# Selector_Gain.net
KiCad netlist of a schematic drawn in EAGLE
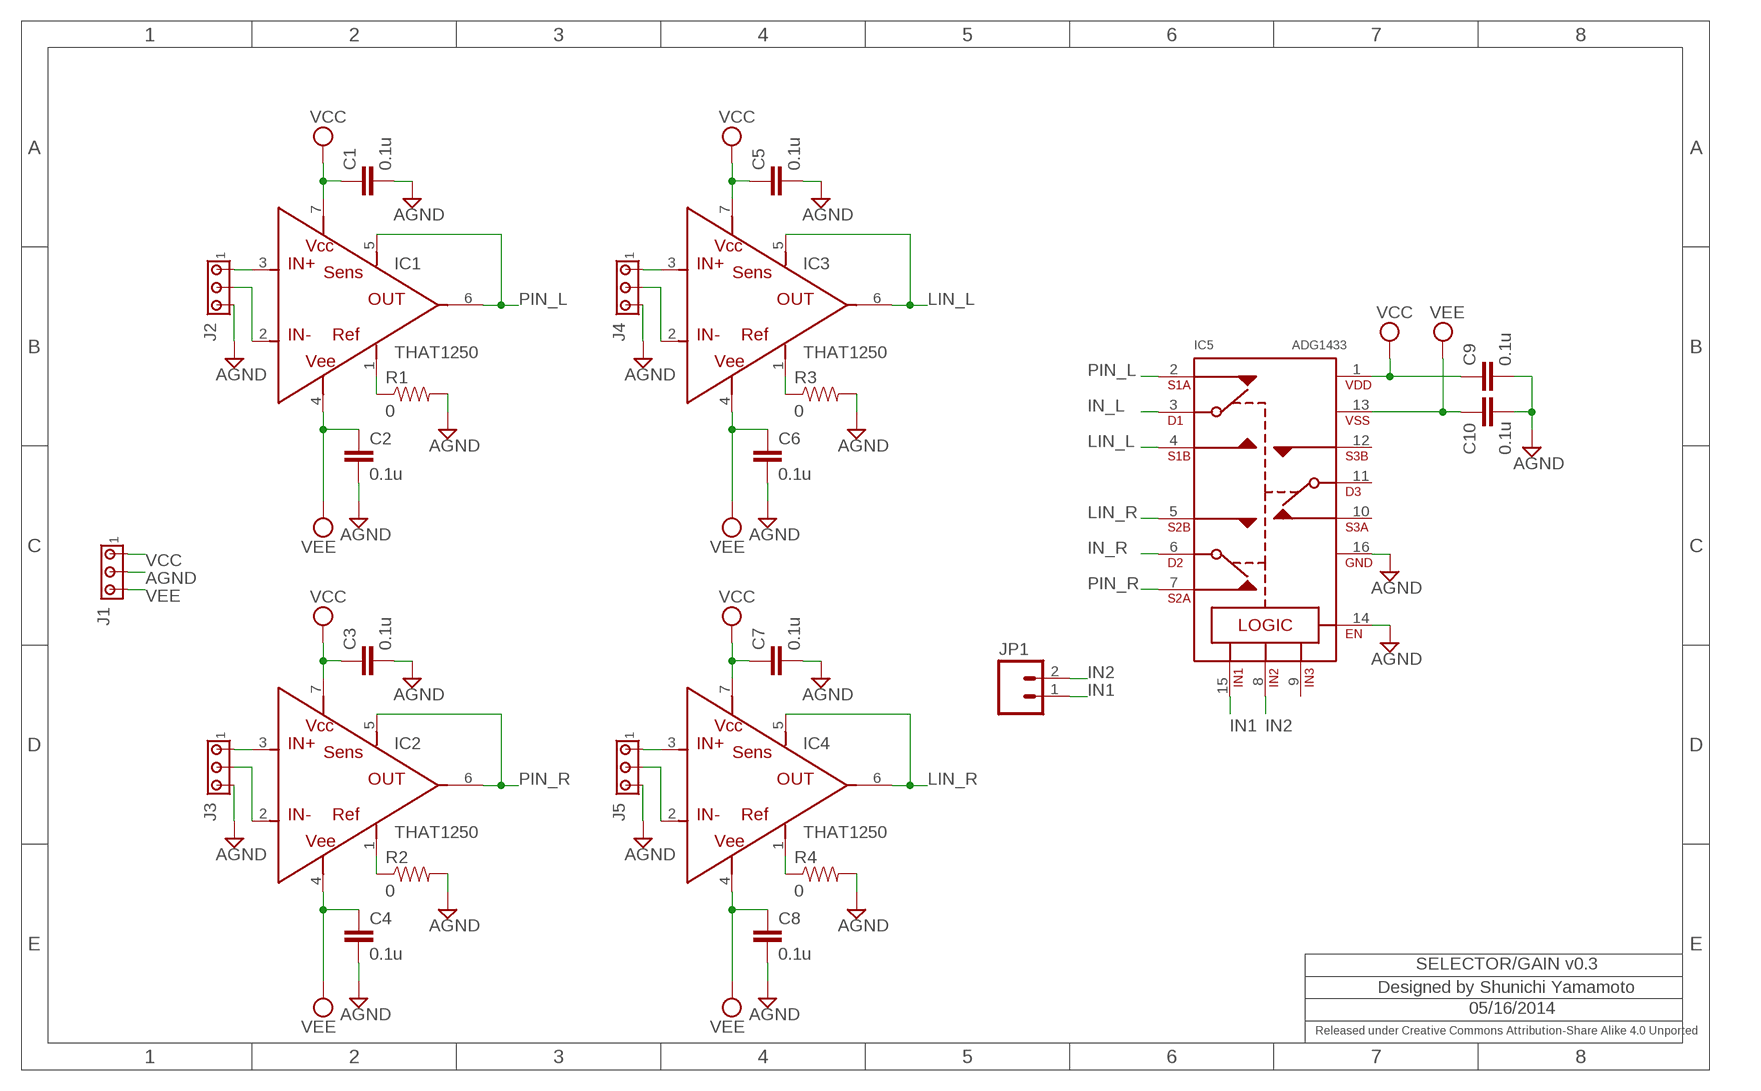
[diagram p0: schematic, sheet 1]
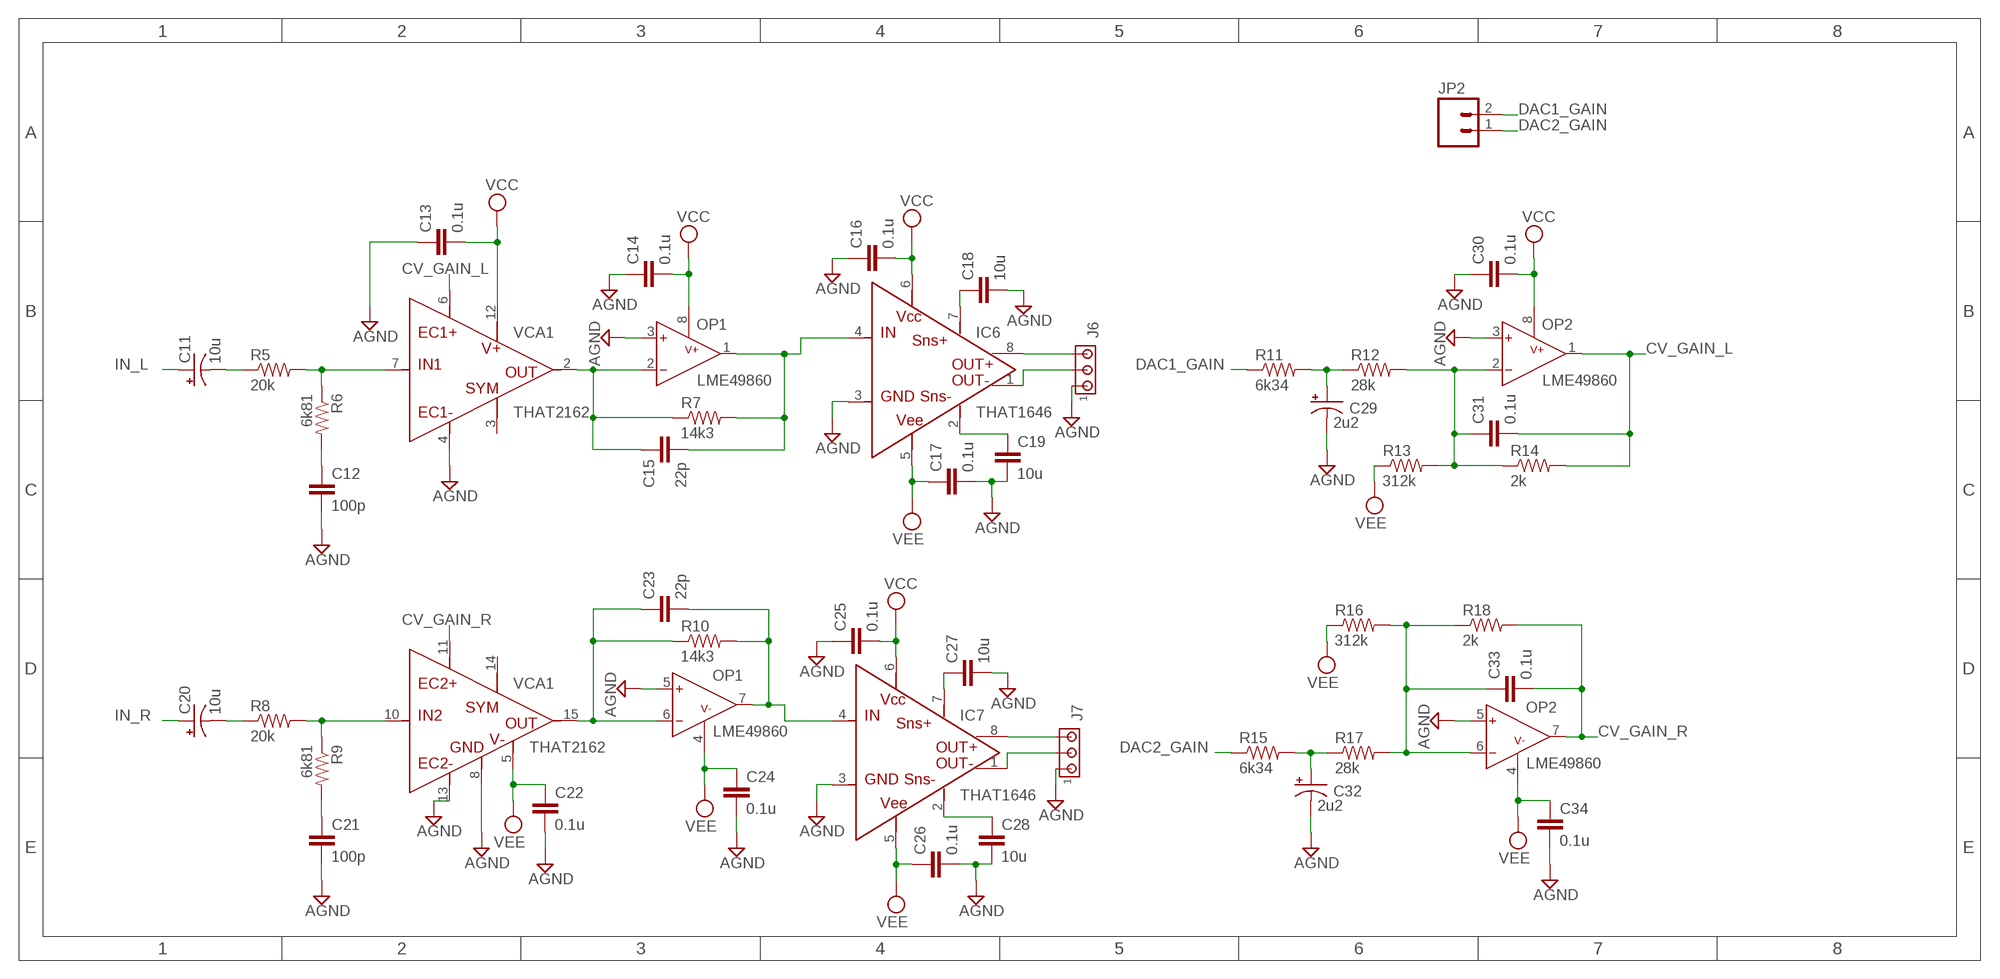
[diagram p1: schematic, sheet 2]

(export (version "E")
  (design (tool "Eeschema 10.0.6"))
  (components
    (comp (ref "C11")
      (value "10u")
      (footprint "eagle-import:UD-5X5,8_NICHICON")
      (libsource (lib "eagle-import") (part "CPOL-USUD-5X5,8"))
    )
    (comp (ref "C12")
      (value "100p")
      (footprint "eagle-import:C2012")
      (libsource (lib "eagle-import") (part "C-EUC2012"))
    )
    (comp (ref "C13")
      (value "0.1u")
      (footprint "eagle-import:C2012")
      (libsource (lib "eagle-import") (part "C-EUC2012"))
    )
    (comp (ref "C14")
      (value "0.1u")
      (footprint "eagle-import:C2012")
      (libsource (lib "eagle-import") (part "C-EUC2012"))
    )
    (comp (ref "C15")
      (value "22p")
      (footprint "eagle-import:C2012")
      (libsource (lib "eagle-import") (part "C-EUC2012"))
    )
    (comp (ref "C16")
      (value "0.1u")
      (footprint "eagle-import:C2012")
      (libsource (lib "eagle-import") (part "C-EUC2012"))
    )
    (comp (ref "C17")
      (value "0.1u")
      (footprint "eagle-import:C2012")
      (libsource (lib "eagle-import") (part "C-EUC2012"))
    )
    (comp (ref "C18")
      (value "10u")
      (footprint "eagle-import:C2012")
      (libsource (lib "eagle-import") (part "C-EUC2012"))
    )
    (comp (ref "C19")
      (value "10u")
      (footprint "eagle-import:C2012")
      (libsource (lib "eagle-import") (part "C-EUC2012"))
    )
    (comp (ref "C20")
      (value "10u")
      (footprint "eagle-import:UD-5X5,8_NICHICON")
      (libsource (lib "eagle-import") (part "CPOL-USUD-5X5,8"))
    )
    (comp (ref "C21")
      (value "100p")
      (footprint "eagle-import:C2012")
      (libsource (lib "eagle-import") (part "C-EUC2012"))
    )
    (comp (ref "C22")
      (value "0.1u")
      (footprint "eagle-import:C2012")
      (libsource (lib "eagle-import") (part "C-EUC2012"))
    )
    (comp (ref "C23")
      (value "22p")
      (footprint "eagle-import:C2012")
      (libsource (lib "eagle-import") (part "C-EUC2012"))
    )
    (comp (ref "C24")
      (value "0.1u")
      (footprint "eagle-import:C2012")
      (libsource (lib "eagle-import") (part "C-EUC2012"))
    )
    (comp (ref "C25")
      (value "0.1u")
      (footprint "eagle-import:C2012")
      (libsource (lib "eagle-import") (part "C-EUC2012"))
    )
    (comp (ref "C26")
      (value "0.1u")
      (footprint "eagle-import:C2012")
      (libsource (lib "eagle-import") (part "C-EUC2012"))
    )
    (comp (ref "C27")
      (value "10u")
      (footprint "eagle-import:C2012")
      (libsource (lib "eagle-import") (part "C-EUC2012"))
    )
    (comp (ref "C28")
      (value "10u")
      (footprint "eagle-import:C2012")
      (libsource (lib "eagle-import") (part "C-EUC2012"))
    )
    (comp (ref "C29")
      (value "2u2")
      (footprint "eagle-import:UD-5X5,8_NICHICON")
      (libsource (lib "eagle-import") (part "CPOL-USUD-5X5,8"))
    )
    (comp (ref "C30")
      (value "0.1u")
      (footprint "eagle-import:C2012")
      (libsource (lib "eagle-import") (part "C-EUC2012"))
    )
    (comp (ref "C31")
      (value "0.1u")
      (footprint "eagle-import:C2012")
      (libsource (lib "eagle-import") (part "C-EUC2012"))
    )
    (comp (ref "C32")
      (value "2u2")
      (footprint "eagle-import:UD-5X5,8_NICHICON")
      (libsource (lib "eagle-import") (part "CPOL-USUD-5X5,8"))
    )
    (comp (ref "C33")
      (value "0.1u")
      (footprint "eagle-import:C2012")
      (libsource (lib "eagle-import") (part "C-EUC2012"))
    )
    (comp (ref "C34")
      (value "0.1u")
      (footprint "eagle-import:C2012")
      (libsource (lib "eagle-import") (part "C-EUC2012"))
    )
    (comp (ref "IC6")
      (value "THAT1646")
      (footprint "eagle-import:SOIC8")
      (libsource (lib "eagle-import") (part "THAT1646"))
    )
    (comp (ref "IC7")
      (value "THAT1646")
      (footprint "eagle-import:SOIC8")
      (libsource (lib "eagle-import") (part "THAT1646"))
    )
    (comp (ref "J6")
      (value "MTA03-100")
      (footprint "eagle-import:10X03MTA")
      (libsource (lib "eagle-import") (part "MTA03-100"))
    )
    (comp (ref "J7")
      (value "MTA03-100")
      (footprint "eagle-import:10X03MTA")
      (libsource (lib "eagle-import") (part "MTA03-100"))
    )
    (comp (ref "JP2")
      (value "M02PTH")
      (footprint "eagle-import:1X02")
      (libsource (lib "eagle-import") (part "M02PTH"))
    )
    (comp (ref "OP1")
      (value "LME49860")
      (footprint "eagle-import:SOIC8")
      (libsource (lib "eagle-import") (part "LME49860"))
    )
    (comp (ref "OP2")
      (value "LME49860")
      (footprint "eagle-import:SOIC8")
      (libsource (lib "eagle-import") (part "LME49860"))
    )
    (comp (ref "R5")
      (value "20k")
      (footprint "eagle-import:0805")
      (libsource (lib "eagle-import") (part "RESISTOR0805-RES"))
    )
    (comp (ref "R6")
      (value "6k81")
      (footprint "eagle-import:0805")
      (libsource (lib "eagle-import") (part "RESISTOR0805-RES"))
    )
    (comp (ref "R7")
      (value "14k3")
      (footprint "eagle-import:0805")
      (libsource (lib "eagle-import") (part "RESISTOR0805-RES"))
    )
    (comp (ref "R8")
      (value "20k")
      (footprint "eagle-import:0805")
      (libsource (lib "eagle-import") (part "RESISTOR0805-RES"))
    )
    (comp (ref "R9")
      (value "6k81")
      (footprint "eagle-import:0805")
      (libsource (lib "eagle-import") (part "RESISTOR0805-RES"))
    )
    (comp (ref "R10")
      (value "14k3")
      (footprint "eagle-import:0805")
      (libsource (lib "eagle-import") (part "RESISTOR0805-RES"))
    )
    (comp (ref "R11")
      (value "6k34")
      (footprint "eagle-import:0805")
      (libsource (lib "eagle-import") (part "RESISTOR0805-RES"))
    )
    (comp (ref "R12")
      (value "28k")
      (footprint "eagle-import:0805")
      (libsource (lib "eagle-import") (part "RESISTOR0805-RES"))
    )
    (comp (ref "R13")
      (value "312k")
      (footprint "eagle-import:0805")
      (libsource (lib "eagle-import") (part "RESISTOR0805-RES"))
    )
    (comp (ref "R14")
      (value "2k")
      (footprint "eagle-import:0805")
      (libsource (lib "eagle-import") (part "RESISTOR0805-RES"))
    )
    (comp (ref "R15")
      (value "6k34")
      (footprint "eagle-import:0805")
      (libsource (lib "eagle-import") (part "RESISTOR0805-RES"))
    )
    (comp (ref "R16")
      (value "312k")
      (footprint "eagle-import:0805")
      (libsource (lib "eagle-import") (part "RESISTOR0805-RES"))
    )
    (comp (ref "R17")
      (value "28k")
      (footprint "eagle-import:0805")
      (libsource (lib "eagle-import") (part "RESISTOR0805-RES"))
    )
    (comp (ref "R18")
      (value "2k")
      (footprint "eagle-import:0805")
      (libsource (lib "eagle-import") (part "RESISTOR0805-RES"))
    )
    (comp (ref "VCA1")
      (value "THAT2162")
      (footprint "eagle-import:QSOP-16")
      (libsource (lib "eagle-import") (part "THAT2162"))
    )
    (comp (ref "C1")
      (value "0.1u")
      (footprint "eagle-import:C2012")
      (libsource (lib "eagle-import") (part "C-EUC2012"))
    )
    (comp (ref "C2")
      (value "0.1u")
      (footprint "eagle-import:C2012")
      (libsource (lib "eagle-import") (part "C-EUC2012"))
    )
    (comp (ref "C3")
      (value "0.1u")
      (footprint "eagle-import:C2012")
      (libsource (lib "eagle-import") (part "C-EUC2012"))
    )
    (comp (ref "C4")
      (value "0.1u")
      (footprint "eagle-import:C2012")
      (libsource (lib "eagle-import") (part "C-EUC2012"))
    )
    (comp (ref "C5")
      (value "0.1u")
      (footprint "eagle-import:C2012")
      (libsource (lib "eagle-import") (part "C-EUC2012"))
    )
    (comp (ref "C6")
      (value "0.1u")
      (footprint "eagle-import:C2012")
      (libsource (lib "eagle-import") (part "C-EUC2012"))
    )
    (comp (ref "C7")
      (value "0.1u")
      (footprint "eagle-import:C2012")
      (libsource (lib "eagle-import") (part "C-EUC2012"))
    )
    (comp (ref "C8")
      (value "0.1u")
      (footprint "eagle-import:C2012")
      (libsource (lib "eagle-import") (part "C-EUC2012"))
    )
    (comp (ref "C9")
      (value "0.1u")
      (footprint "eagle-import:C2012")
      (libsource (lib "eagle-import") (part "C-EUC2012"))
    )
    (comp (ref "C10")
      (value "0.1u")
      (footprint "eagle-import:C2012")
      (libsource (lib "eagle-import") (part "C-EUC2012"))
    )
    (comp (ref "IC1")
      (value "THAT1250")
      (footprint "eagle-import:SOIC8")
      (libsource (lib "eagle-import") (part "THAT1250"))
    )
    (comp (ref "IC2")
      (value "THAT1250")
      (footprint "eagle-import:SOIC8")
      (libsource (lib "eagle-import") (part "THAT1250"))
    )
    (comp (ref "IC3")
      (value "THAT1250")
      (footprint "eagle-import:SOIC8")
      (libsource (lib "eagle-import") (part "THAT1250"))
    )
    (comp (ref "IC4")
      (value "THAT1250")
      (footprint "eagle-import:SOIC8")
      (libsource (lib "eagle-import") (part "THAT1250"))
    )
    (comp (ref "IC5")
      (value "ADG1433")
      (footprint "eagle-import:TSSOP16")
      (libsource (lib "eagle-import") (part "ADG1433"))
    )
    (comp (ref "J1")
      (value "MTA03-156")
      (footprint "eagle-import:1X3MTA")
      (libsource (lib "eagle-import") (part "MTA03-156"))
    )
    (comp (ref "J2")
      (value "MTA03-100")
      (footprint "eagle-import:10X03MTA")
      (libsource (lib "eagle-import") (part "MTA03-100"))
    )
    (comp (ref "J3")
      (value "MTA03-100")
      (footprint "eagle-import:10X03MTA")
      (libsource (lib "eagle-import") (part "MTA03-100"))
    )
    (comp (ref "J4")
      (value "MTA03-100")
      (footprint "eagle-import:10X03MTA")
      (libsource (lib "eagle-import") (part "MTA03-100"))
    )
    (comp (ref "J5")
      (value "MTA03-100")
      (footprint "eagle-import:10X03MTA")
      (libsource (lib "eagle-import") (part "MTA03-100"))
    )
    (comp (ref "JP1")
      (value "M02PTH")
      (footprint "eagle-import:1X02")
      (libsource (lib "eagle-import") (part "M02PTH"))
    )
    (comp (ref "R1")
      (value "0")
      (footprint "eagle-import:0805")
      (libsource (lib "eagle-import") (part "RESISTOR0805-RES"))
    )
    (comp (ref "R2")
      (value "0")
      (footprint "eagle-import:0805")
      (libsource (lib "eagle-import") (part "RESISTOR0805-RES"))
    )
    (comp (ref "R3")
      (value "0")
      (footprint "eagle-import:0805")
      (libsource (lib "eagle-import") (part "RESISTOR0805-RES"))
    )
    (comp (ref "R4")
      (value "0")
      (footprint "eagle-import:0805")
      (libsource (lib "eagle-import") (part "RESISTOR0805-RES"))
    )
  )
  (nets
    (net (code "1") (name "AGND") (class "Default")
      (node (ref "C1") (pin "2") (pinfunction "2_2") (pintype "passive"))
      (node (ref "C10") (pin "2") (pinfunction "2_2") (pintype "passive"))
      (node (ref "C12") (pin "2") (pinfunction "2_2") (pintype "passive"))
      (node (ref "C13") (pin "1") (pinfunction "1_1") (pintype "passive"))
      (node (ref "C14") (pin "1") (pinfunction "1_1") (pintype "passive"))
      (node (ref "C16") (pin "1") (pinfunction "1_1") (pintype "passive"))
      (node (ref "C17") (pin "2") (pinfunction "2_2") (pintype "passive"))
      (node (ref "C18") (pin "2") (pinfunction "2_2") (pintype "passive"))
      (node (ref "C19") (pin "2") (pinfunction "2_2") (pintype "passive"))
      (node (ref "C2") (pin "2") (pinfunction "2_2") (pintype "passive"))
      (node (ref "C21") (pin "2") (pinfunction "2_2") (pintype "passive"))
      (node (ref "C22") (pin "2") (pinfunction "2_2") (pintype "passive"))
      (node (ref "C24") (pin "2") (pinfunction "2_2") (pintype "passive"))
      (node (ref "C25") (pin "1") (pinfunction "1_1") (pintype "passive"))
      (node (ref "C26") (pin "2") (pinfunction "2_2") (pintype "passive"))
      (node (ref "C27") (pin "2") (pinfunction "2_2") (pintype "passive"))
      (node (ref "C28") (pin "2") (pinfunction "2_2") (pintype "passive"))
      (node (ref "C29") (pin "-") (pinfunction "-_-") (pintype "passive"))
      (node (ref "C3") (pin "2") (pinfunction "2_2") (pintype "passive"))
      (node (ref "C30") (pin "1") (pinfunction "1_1") (pintype "passive"))
      (node (ref "C32") (pin "-") (pinfunction "-_-") (pintype "passive"))
      (node (ref "C34") (pin "2") (pinfunction "2_2") (pintype "passive"))
      (node (ref "C4") (pin "2") (pinfunction "2_2") (pintype "passive"))
      (node (ref "C5") (pin "2") (pinfunction "2_2") (pintype "passive"))
      (node (ref "C6") (pin "2") (pinfunction "2_2") (pintype "passive"))
      (node (ref "C7") (pin "2") (pinfunction "2_2") (pintype "passive"))
      (node (ref "C8") (pin "2") (pinfunction "2_2") (pintype "passive"))
      (node (ref "C9") (pin "2") (pinfunction "2_2") (pintype "passive"))
      (node (ref "IC5") (pin "14") (pinfunction "EN_14") (pintype "bidirectional"))
      (node (ref "IC5") (pin "16") (pinfunction "GND_16") (pintype "bidirectional"))
      (node (ref "IC6") (pin "3") (pinfunction "GND_3") (pintype "input"))
      (node (ref "IC7") (pin "3") (pinfunction "GND_3") (pintype "input"))
      (node (ref "J1") (pin "2") (pinfunction "2_2") (pintype "passive"))
      (node (ref "J2") (pin "3") (pinfunction "3_3") (pintype "passive"))
      (node (ref "J3") (pin "3") (pinfunction "3_3") (pintype "passive"))
      (node (ref "J4") (pin "3") (pinfunction "3_3") (pintype "passive"))
      (node (ref "J5") (pin "3") (pinfunction "3_3") (pintype "passive"))
      (node (ref "J6") (pin "1") (pinfunction "1_1") (pintype "passive"))
      (node (ref "J7") (pin "1") (pinfunction "1_1") (pintype "passive"))
      (node (ref "OP1") (pin "3") (pinfunction "INA+_3") (pintype "input"))
      (node (ref "OP1") (pin "5") (pinfunction "INB+_5") (pintype "input"))
      (node (ref "OP2") (pin "3") (pinfunction "INA+_3") (pintype "input"))
      (node (ref "OP2") (pin "5") (pinfunction "INB+_5") (pintype "input"))
      (node (ref "R1") (pin "2") (pinfunction "2_2") (pintype "passive"))
      (node (ref "R2") (pin "2") (pinfunction "2_2") (pintype "passive"))
      (node (ref "R3") (pin "2") (pinfunction "2_2") (pintype "passive"))
      (node (ref "R4") (pin "2") (pinfunction "2_2") (pintype "passive"))
      (node (ref "VCA1") (pin "13") (pinfunction "EC2-_13") (pintype "power_in"))
      (node (ref "VCA1") (pin "4") (pinfunction "EC1-_4") (pintype "input"))
      (node (ref "VCA1") (pin "8") (pinfunction "GND_8") (pintype "input"))
    )
    (net (code "2") (name "CV_GAIN_L") (class "Default")
      (node (ref "C31") (pin "2") (pinfunction "2_2") (pintype "passive"))
      (node (ref "OP2") (pin "1") (pinfunction "OUTA_1") (pintype "output"))
      (node (ref "R14") (pin "2") (pinfunction "2_2") (pintype "passive"))
      (node (ref "VCA1") (pin "6") (pinfunction "EC1+_6") (pintype "bidirectional"))
    )
    (net (code "3") (name "CV_GAIN_R") (class "Default")
      (node (ref "C33") (pin "2") (pinfunction "2_2") (pintype "passive"))
      (node (ref "OP2") (pin "7") (pinfunction "OUTB_7") (pintype "output"))
      (node (ref "R18") (pin "2") (pinfunction "2_2") (pintype "passive"))
      (node (ref "VCA1") (pin "11") (pinfunction "EC2+_11") (pintype "input"))
    )
    (net (code "4") (name "DAC1_GAIN") (class "Default")
      (node (ref "JP2") (pin "2") (pinfunction "2_2") (pintype "passive"))
      (node (ref "R11") (pin "1") (pinfunction "1_1") (pintype "passive"))
    )
    (net (code "5") (name "DAC2_GAIN") (class "Default")
      (node (ref "JP2") (pin "1") (pinfunction "1_1") (pintype "passive"))
      (node (ref "R15") (pin "1") (pinfunction "1_1") (pintype "passive"))
    )
    (net (code "6") (name "IN1") (class "Default")
      (node (ref "IC5") (pin "15") (pinfunction "IN1_15") (pintype "bidirectional"))
      (node (ref "JP1") (pin "1") (pinfunction "1_1") (pintype "passive"))
    )
    (net (code "7") (name "IN2") (class "Default")
      (node (ref "IC5") (pin "8") (pinfunction "IN2_8") (pintype "bidirectional"))
      (node (ref "JP1") (pin "2") (pinfunction "2_2") (pintype "passive"))
    )
    (net (code "8") (name "IN_L") (class "Default")
      (node (ref "C11") (pin "+") (pinfunction "+_+") (pintype "passive"))
      (node (ref "IC5") (pin "3") (pinfunction "D1_3") (pintype "bidirectional"))
    )
    (net (code "9") (name "IN_R") (class "Default")
      (node (ref "C20") (pin "+") (pinfunction "+_+") (pintype "passive"))
      (node (ref "IC5") (pin "6") (pinfunction "D2_6") (pintype "bidirectional"))
    )
    (net (code "10") (name "LIN_L") (class "Default")
      (node (ref "IC3") (pin "5") (pinfunction "SENS_5") (pintype "power_in"))
      (node (ref "IC3") (pin "6") (pinfunction "OUT_6") (pintype "output"))
      (node (ref "IC5") (pin "4") (pinfunction "S1B_4") (pintype "bidirectional"))
    )
    (net (code "11") (name "LIN_R") (class "Default")
      (node (ref "IC4") (pin "5") (pinfunction "SENS_5") (pintype "power_in"))
      (node (ref "IC4") (pin "6") (pinfunction "OUT_6") (pintype "output"))
      (node (ref "IC5") (pin "5") (pinfunction "S2B_5") (pintype "bidirectional"))
    )
    (net (code "12") (name "Net-(C11-Pad-)") (class "Default")
      (node (ref "C11") (pin "-") (pinfunction "-_-") (pintype "passive"))
      (node (ref "R5") (pin "1") (pinfunction "1_1") (pintype "passive"))
    )
    (net (code "13") (name "Net-(C12-Pad1)") (class "Default")
      (node (ref "C12") (pin "1") (pinfunction "1_1") (pintype "passive"))
      (node (ref "R6") (pin "2") (pinfunction "2_2") (pintype "passive"))
    )
    (net (code "14") (name "Net-(C20-Pad-)") (class "Default")
      (node (ref "C20") (pin "-") (pinfunction "-_-") (pintype "passive"))
      (node (ref "R8") (pin "1") (pinfunction "1_1") (pintype "passive"))
    )
    (net (code "15") (name "Net-(C21-Pad1)") (class "Default")
      (node (ref "C21") (pin "1") (pinfunction "1_1") (pintype "passive"))
      (node (ref "R9") (pin "2") (pinfunction "2_2") (pintype "passive"))
    )
    (net (code "16") (name "Net-(C29-Pad+)") (class "Default")
      (node (ref "C29") (pin "+") (pinfunction "+_+") (pintype "passive"))
      (node (ref "R11") (pin "2") (pinfunction "2_2") (pintype "passive"))
      (node (ref "R12") (pin "1") (pinfunction "1_1") (pintype "passive"))
    )
    (net (code "17") (name "Net-(C32-Pad+)") (class "Default")
      (node (ref "C32") (pin "+") (pinfunction "+_+") (pintype "passive"))
      (node (ref "R15") (pin "2") (pinfunction "2_2") (pintype "passive"))
      (node (ref "R17") (pin "1") (pinfunction "1_1") (pintype "passive"))
    )
    (net (code "18") (name "Net-(IC1-IN+)") (class "Default")
      (node (ref "IC1") (pin "3") (pinfunction "IN+_3") (pintype "input"))
      (node (ref "J2") (pin "1") (pinfunction "1_1") (pintype "passive"))
    )
    (net (code "19") (name "Net-(IC1-IN-)") (class "Default")
      (node (ref "IC1") (pin "2") (pinfunction "IN-_2") (pintype "input"))
      (node (ref "J2") (pin "2") (pinfunction "2_2") (pintype "passive"))
    )
    (net (code "20") (name "Net-(IC1-REF)") (class "Default")
      (node (ref "IC1") (pin "1") (pinfunction "REF_1") (pintype "input"))
      (node (ref "R1") (pin "1") (pinfunction "1_1") (pintype "passive"))
    )
    (net (code "21") (name "Net-(IC2-IN+)") (class "Default")
      (node (ref "IC2") (pin "3") (pinfunction "IN+_3") (pintype "input"))
      (node (ref "J3") (pin "1") (pinfunction "1_1") (pintype "passive"))
    )
    (net (code "22") (name "Net-(IC2-IN-)") (class "Default")
      (node (ref "IC2") (pin "2") (pinfunction "IN-_2") (pintype "input"))
      (node (ref "J3") (pin "2") (pinfunction "2_2") (pintype "passive"))
    )
    (net (code "23") (name "Net-(IC2-REF)") (class "Default")
      (node (ref "IC2") (pin "1") (pinfunction "REF_1") (pintype "input"))
      (node (ref "R2") (pin "1") (pinfunction "1_1") (pintype "passive"))
    )
    (net (code "24") (name "Net-(IC3-IN+)") (class "Default")
      (node (ref "IC3") (pin "3") (pinfunction "IN+_3") (pintype "input"))
      (node (ref "J4") (pin "1") (pinfunction "1_1") (pintype "passive"))
    )
    (net (code "25") (name "Net-(IC3-IN-)") (class "Default")
      (node (ref "IC3") (pin "2") (pinfunction "IN-_2") (pintype "input"))
      (node (ref "J4") (pin "2") (pinfunction "2_2") (pintype "passive"))
    )
    (net (code "26") (name "Net-(IC3-REF)") (class "Default")
      (node (ref "IC3") (pin "1") (pinfunction "REF_1") (pintype "input"))
      (node (ref "R3") (pin "1") (pinfunction "1_1") (pintype "passive"))
    )
    (net (code "27") (name "Net-(IC4-IN+)") (class "Default")
      (node (ref "IC4") (pin "3") (pinfunction "IN+_3") (pintype "input"))
      (node (ref "J5") (pin "1") (pinfunction "1_1") (pintype "passive"))
    )
    (net (code "28") (name "Net-(IC4-IN-)") (class "Default")
      (node (ref "IC4") (pin "2") (pinfunction "IN-_2") (pintype "input"))
      (node (ref "J5") (pin "2") (pinfunction "2_2") (pintype "passive"))
    )
    (net (code "29") (name "Net-(IC4-REF)") (class "Default")
      (node (ref "IC4") (pin "1") (pinfunction "REF_1") (pintype "input"))
      (node (ref "R4") (pin "1") (pinfunction "1_1") (pintype "passive"))
    )
    (net (code "30") (name "Net-(IC6-IN)") (class "Default")
      (node (ref "C15") (pin "2") (pinfunction "2_2") (pintype "passive"))
      (node (ref "IC6") (pin "4") (pinfunction "IN_4") (pintype "input"))
      (node (ref "OP1") (pin "1") (pinfunction "OUTA_1") (pintype "output"))
      (node (ref "R7") (pin "2") (pinfunction "2_2") (pintype "passive"))
    )
    (net (code "31") (name "Net-(IC6-OUT+)") (class "Default")
      (node (ref "IC6") (pin "8") (pinfunction "OUT+_8") (pintype "output"))
      (node (ref "J6") (pin "3") (pinfunction "3_3") (pintype "passive"))
    )
    (net (code "32") (name "Net-(IC6-OUT-)") (class "Default")
      (node (ref "IC6") (pin "1") (pinfunction "OUT-_1") (pintype "output"))
      (node (ref "J6") (pin "2") (pinfunction "2_2") (pintype "passive"))
    )
    (net (code "33") (name "Net-(IC6-SNS+)") (class "Default")
      (node (ref "C18") (pin "1") (pinfunction "1_1") (pintype "passive"))
      (node (ref "IC6") (pin "7") (pinfunction "SNS+_7") (pintype "power_in"))
    )
    (net (code "34") (name "Net-(IC6-SNS-)") (class "Default")
      (node (ref "C19") (pin "1") (pinfunction "1_1") (pintype "passive"))
      (node (ref "IC6") (pin "2") (pinfunction "SNS-_2") (pintype "input"))
    )
    (net (code "35") (name "Net-(IC7-IN)") (class "Default")
      (node (ref "C23") (pin "2") (pinfunction "2_2") (pintype "passive"))
      (node (ref "IC7") (pin "4") (pinfunction "IN_4") (pintype "input"))
      (node (ref "OP1") (pin "7") (pinfunction "OUTB_7") (pintype "output"))
      (node (ref "R10") (pin "2") (pinfunction "2_2") (pintype "passive"))
    )
    (net (code "36") (name "Net-(IC7-OUT+)") (class "Default")
      (node (ref "IC7") (pin "8") (pinfunction "OUT+_8") (pintype "output"))
      (node (ref "J7") (pin "3") (pinfunction "3_3") (pintype "passive"))
    )
    (net (code "37") (name "Net-(IC7-OUT-)") (class "Default")
      (node (ref "IC7") (pin "1") (pinfunction "OUT-_1") (pintype "output"))
      (node (ref "J7") (pin "2") (pinfunction "2_2") (pintype "passive"))
    )
    (net (code "38") (name "Net-(IC7-SNS+)") (class "Default")
      (node (ref "C27") (pin "1") (pinfunction "1_1") (pintype "passive"))
      (node (ref "IC7") (pin "7") (pinfunction "SNS+_7") (pintype "power_in"))
    )
    (net (code "39") (name "Net-(IC7-SNS-)") (class "Default")
      (node (ref "C28") (pin "1") (pinfunction "1_1") (pintype "passive"))
      (node (ref "IC7") (pin "2") (pinfunction "SNS-_2") (pintype "input"))
    )
    (net (code "40") (name "Net-(OP1A-INA-)") (class "Default")
      (node (ref "C15") (pin "1") (pinfunction "1_1") (pintype "passive"))
      (node (ref "OP1") (pin "2") (pinfunction "INA-_2") (pintype "input"))
      (node (ref "R7") (pin "1") (pinfunction "1_1") (pintype "passive"))
      (node (ref "VCA1") (pin "2") (pinfunction "OUT1_2") (pintype "output"))
    )
    (net (code "41") (name "Net-(OP1B-INB-)") (class "Default")
      (node (ref "C23") (pin "1") (pinfunction "1_1") (pintype "passive"))
      (node (ref "OP1") (pin "6") (pinfunction "INB-_6") (pintype "input"))
      (node (ref "R10") (pin "1") (pinfunction "1_1") (pintype "passive"))
      (node (ref "VCA1") (pin "15") (pinfunction "OUT2_15") (pintype "output"))
    )
    (net (code "42") (name "Net-(OP2A-INA-)") (class "Default")
      (node (ref "C31") (pin "1") (pinfunction "1_1") (pintype "passive"))
      (node (ref "OP2") (pin "2") (pinfunction "INA-_2") (pintype "input"))
      (node (ref "R12") (pin "2") (pinfunction "2_2") (pintype "passive"))
      (node (ref "R13") (pin "2") (pinfunction "2_2") (pintype "passive"))
      (node (ref "R14") (pin "1") (pinfunction "1_1") (pintype "passive"))
    )
    (net (code "43") (name "Net-(OP2B-INB-)") (class "Default")
      (node (ref "C33") (pin "1") (pinfunction "1_1") (pintype "passive"))
      (node (ref "OP2") (pin "6") (pinfunction "INB-_6") (pintype "input"))
      (node (ref "R16") (pin "2") (pinfunction "2_2") (pintype "passive"))
      (node (ref "R17") (pin "2") (pinfunction "2_2") (pintype "passive"))
      (node (ref "R18") (pin "1") (pinfunction "1_1") (pintype "passive"))
    )
    (net (code "44") (name "Net-(VCA1A-IN1)") (class "Default")
      (node (ref "R5") (pin "2") (pinfunction "2_2") (pintype "passive"))
      (node (ref "R6") (pin "1") (pinfunction "1_1") (pintype "passive"))
      (node (ref "VCA1") (pin "7") (pinfunction "IN1_7") (pintype "input"))
    )
    (net (code "45") (name "Net-(VCA1B-IN2)") (class "Default")
      (node (ref "R8") (pin "2") (pinfunction "2_2") (pintype "passive"))
      (node (ref "R9") (pin "1") (pinfunction "1_1") (pintype "passive"))
      (node (ref "VCA1") (pin "10") (pinfunction "IN2_10") (pintype "input"))
    )
    (net (code "46") (name "PIN_L") (class "Default")
      (node (ref "IC1") (pin "5") (pinfunction "SENS_5") (pintype "power_in"))
      (node (ref "IC1") (pin "6") (pinfunction "OUT_6") (pintype "output"))
      (node (ref "IC5") (pin "2") (pinfunction "S1A_2") (pintype "bidirectional"))
    )
    (net (code "47") (name "PIN_R") (class "Default")
      (node (ref "IC2") (pin "5") (pinfunction "SENS_5") (pintype "power_in"))
      (node (ref "IC2") (pin "6") (pinfunction "OUT_6") (pintype "output"))
      (node (ref "IC5") (pin "7") (pinfunction "S2A_7") (pintype "bidirectional"))
    )
    (net (code "48") (name "VCC") (class "Default")
      (node (ref "C1") (pin "1") (pinfunction "1_1") (pintype "passive"))
      (node (ref "C13") (pin "2") (pinfunction "2_2") (pintype "passive"))
      (node (ref "C14") (pin "2") (pinfunction "2_2") (pintype "passive"))
      (node (ref "C16") (pin "2") (pinfunction "2_2") (pintype "passive"))
      (node (ref "C25") (pin "2") (pinfunction "2_2") (pintype "passive"))
      (node (ref "C3") (pin "1") (pinfunction "1_1") (pintype "passive"))
      (node (ref "C30") (pin "2") (pinfunction "2_2") (pintype "passive"))
      (node (ref "C5") (pin "1") (pinfunction "1_1") (pintype "passive"))
      (node (ref "C7") (pin "1") (pinfunction "1_1") (pintype "passive"))
      (node (ref "C9") (pin "1") (pinfunction "1_1") (pintype "passive"))
      (node (ref "IC1") (pin "7") (pinfunction "VCC_7") (pintype "power_in"))
      (node (ref "IC2") (pin "7") (pinfunction "VCC_7") (pintype "power_in"))
      (node (ref "IC3") (pin "7") (pinfunction "VCC_7") (pintype "power_in"))
      (node (ref "IC4") (pin "7") (pinfunction "VCC_7") (pintype "power_in"))
      (node (ref "IC5") (pin "1") (pinfunction "VDD_1") (pintype "bidirectional"))
      (node (ref "IC6") (pin "6") (pinfunction "VCC_6") (pintype "bidirectional"))
      (node (ref "IC7") (pin "6") (pinfunction "VCC_6") (pintype "bidirectional"))
      (node (ref "J1") (pin "1") (pinfunction "1_1") (pintype "passive"))
      (node (ref "OP1") (pin "8") (pinfunction "V+_8") (pintype "power_in"))
      (node (ref "OP2") (pin "8") (pinfunction "V+_8") (pintype "power_in"))
      (node (ref "VCA1") (pin "12") (pinfunction "V+_12") (pintype "power_in"))
    )
    (net (code "49") (name "VEE") (class "Default")
      (node (ref "C10") (pin "1") (pinfunction "1_1") (pintype "passive"))
      (node (ref "C17") (pin "1") (pinfunction "1_1") (pintype "passive"))
      (node (ref "C2") (pin "1") (pinfunction "1_1") (pintype "passive"))
      (node (ref "C22") (pin "1") (pinfunction "1_1") (pintype "passive"))
      (node (ref "C24") (pin "1") (pinfunction "1_1") (pintype "passive"))
      (node (ref "C26") (pin "1") (pinfunction "1_1") (pintype "passive"))
      (node (ref "C34") (pin "1") (pinfunction "1_1") (pintype "passive"))
      (node (ref "C4") (pin "1") (pinfunction "1_1") (pintype "passive"))
      (node (ref "C6") (pin "1") (pinfunction "1_1") (pintype "passive"))
      (node (ref "C8") (pin "1") (pinfunction "1_1") (pintype "passive"))
      (node (ref "IC1") (pin "4") (pinfunction "VEE_4") (pintype "power_in"))
      (node (ref "IC2") (pin "4") (pinfunction "VEE_4") (pintype "power_in"))
      (node (ref "IC3") (pin "4") (pinfunction "VEE_4") (pintype "power_in"))
      (node (ref "IC4") (pin "4") (pinfunction "VEE_4") (pintype "power_in"))
      (node (ref "IC5") (pin "13") (pinfunction "VSS_13") (pintype "bidirectional"))
      (node (ref "IC6") (pin "5") (pinfunction "VEE_5") (pintype "input"))
      (node (ref "IC7") (pin "5") (pinfunction "VEE_5") (pintype "input"))
      (node (ref "J1") (pin "3") (pinfunction "3_3") (pintype "passive"))
      (node (ref "OP1") (pin "4") (pinfunction "V-_4") (pintype "power_in"))
      (node (ref "OP2") (pin "4") (pinfunction "V-_4") (pintype "power_in"))
      (node (ref "R13") (pin "1") (pinfunction "1_1") (pintype "passive"))
      (node (ref "R16") (pin "1") (pinfunction "1_1") (pintype "passive"))
      (node (ref "VCA1") (pin "5") (pinfunction "V-_5") (pintype "input"))
    )
    (net (code "50") (name "unconnected-(IC5-D3-Pad11)") (class "Default")
      (node (ref "IC5") (pin "11") (pinfunction "D3_11") (pintype "bidirectional"))
    )
    (net (code "51") (name "unconnected-(IC5-IN3-Pad9)") (class "Default")
      (node (ref "IC5") (pin "9") (pinfunction "IN3_9") (pintype "bidirectional"))
    )
    (net (code "52") (name "unconnected-(IC5-S3A-Pad10)") (class "Default")
      (node (ref "IC5") (pin "10") (pinfunction "S3A_10") (pintype "bidirectional"))
    )
    (net (code "53") (name "unconnected-(IC5-S3B-Pad12)") (class "Default")
      (node (ref "IC5") (pin "12") (pinfunction "S3B_12") (pintype "bidirectional"))
    )
    (net (code "54") (name "unconnected-(VCA1A-SYM1-Pad3)") (class "Default")
      (node (ref "VCA1") (pin "3") (pinfunction "SYM1_3") (pintype "input"))
    )
    (net (code "55") (name "unconnected-(VCA1B-SYM2-Pad14)") (class "Default")
      (node (ref "VCA1") (pin "14") (pinfunction "SYM2_14") (pintype "input"))
    )
  )
)
